# GR_Propu.net
KiCad netlist of a schematic drawn in Altium Designer
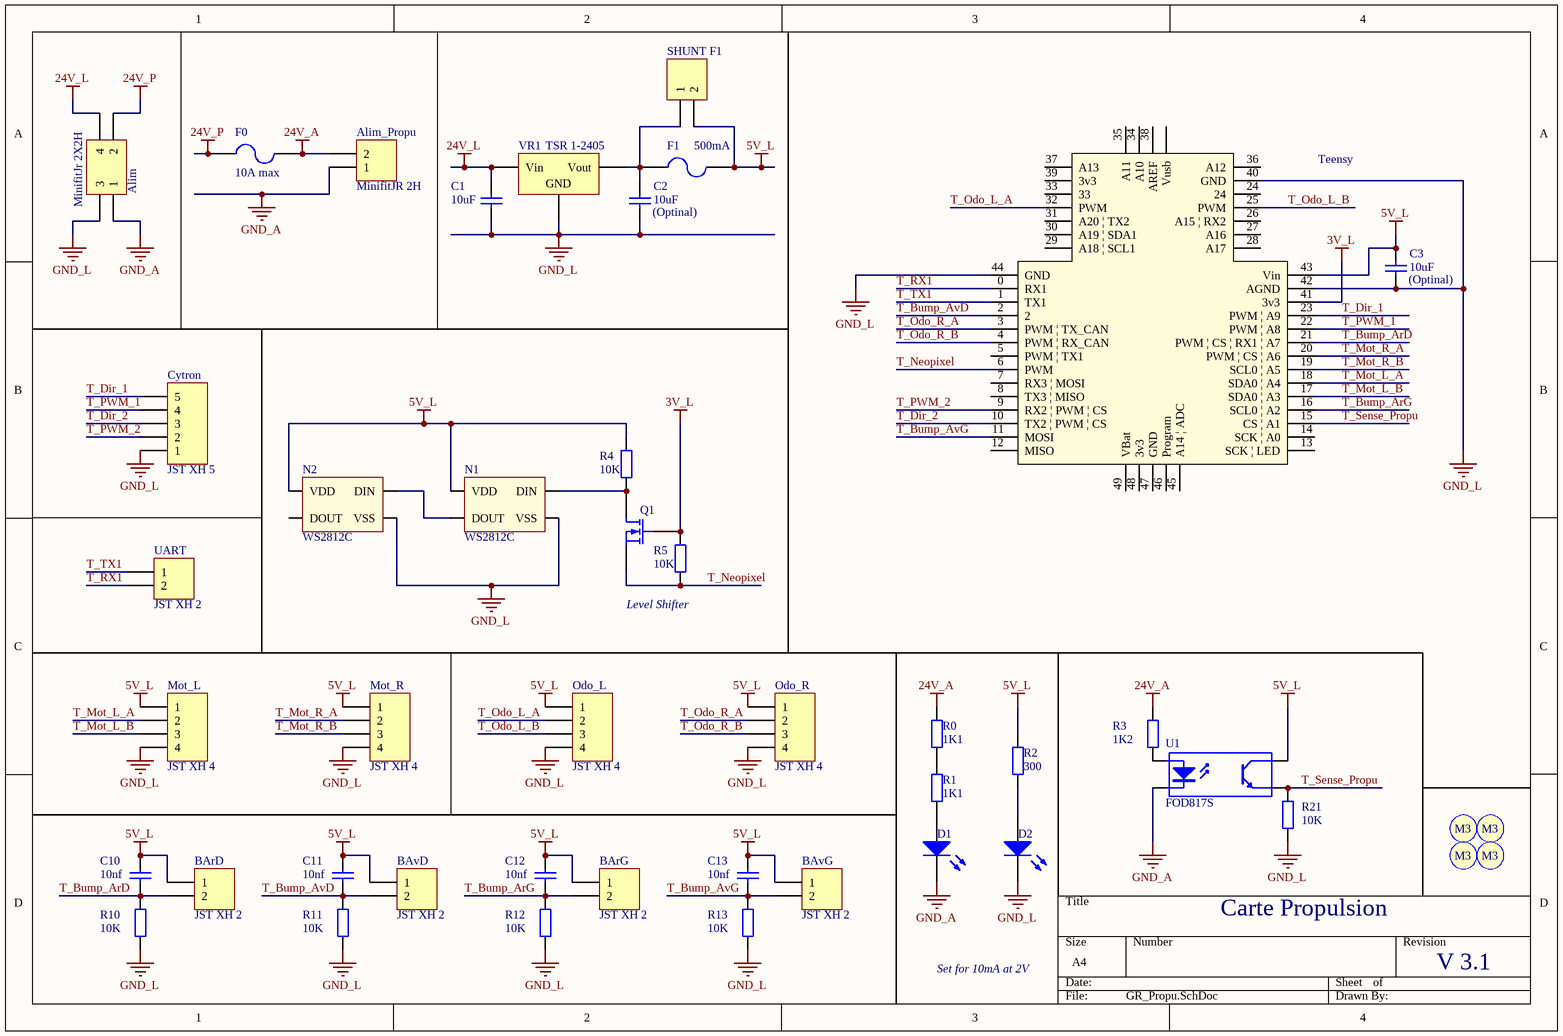
[diagram p0: GR_Propu.SchDoc]

(export (version "E")
  (design (tool "Eeschema 10.0.6"))
  (components
    (comp (ref "Alim")
      (value "MinifitJr 2X2H")
      (footprint "MOLEX_MINIFITJR_2X2H")
      (description "Header, 2-Pin, Dual row, Right Angle")
      (fields (field (name "PUBLISHER") "Altium Limited"))
      (libsource (lib "Miscellaneous Connectors") (part "Header 2X2H"))
    )
    (comp (ref "Alim_Propu")
      (value "MinifitJR 2H")
      (footprint "Molex_MiniFitJr_2x1H")
      (description "Header, 2-Pin")
      (fields (field (name "PUBLISHER") "Altium Limited"))
      (libsource (lib "") (part "Header 2_1"))
    )
    (comp (ref "BArD")
      (value "JST XH 2")
      (footprint "S2B-XH-A")
      (description "Header, 2-Pin")
      (fields (field (name "PUBLISHER") "Altium Limited"))
      (libsource (lib "Miscellaneous Connectors") (part "Header 2"))
    )
    (comp (ref "BArG")
      (value "JST XH 2")
      (footprint "S2B-XH-A")
      (description "Header, 2-Pin")
      (fields (field (name "PUBLISHER") "Altium Limited"))
      (libsource (lib "Miscellaneous Connectors") (part "Header 2"))
    )
    (comp (ref "BAvD")
      (value "JST XH 2")
      (footprint "S2B-XH-A")
      (description "Header, 2-Pin")
      (fields (field (name "PUBLISHER") "Altium Limited"))
      (libsource (lib "Miscellaneous Connectors") (part "Header 2"))
    )
    (comp (ref "BAvG")
      (value "JST XH 2")
      (footprint "S2B-XH-A")
      (description "Header, 2-Pin")
      (fields (field (name "PUBLISHER") "Altium Limited"))
      (libsource (lib "Miscellaneous Connectors") (part "Header 2"))
    )
    (comp (ref "C1")
      (value "10uF")
      (footprint "Capacitor 1206")
      (description "Capacitor")
      (fields (field (name "PUBLISHER") "Altium Limited"))
      (libsource (lib "Miscellaneous Devices") (part "Cap"))
    )
    (comp (ref "C2")
      (value "(Optinal)")
      (footprint "Capacitor 1206")
      (description "Capacitor")
      (fields (field (name "ALTIUM_VALUE") "10uF") (field (name "PUBLISHER") "Altium Limited"))
      (libsource (lib "Miscellaneous Devices") (part "Cap"))
    )
    (comp (ref "C3")
      (value "(Optinal)")
      (footprint "Capacitor 1206")
      (description "Capacitor")
      (fields (field (name "ALTIUM_VALUE") "10uF") (field (name "PUBLISHER") "Altium Limited"))
      (libsource (lib "Miscellaneous Devices") (part "Cap"))
    )
    (comp (ref "C10")
      (value "10nf")
      (footprint "Capacitor 1206")
      (description "Capacitor")
      (fields (field (name "Comment") "Cap") (field (name "PUBLISHER") "Altium Limited"))
      (libsource (lib "Miscellaneous Devices") (part "Cap"))
    )
    (comp (ref "C11")
      (value "10nf")
      (footprint "Capacitor 1206")
      (description "Capacitor")
      (fields (field (name "Comment") "Cap") (field (name "PUBLISHER") "Altium Limited"))
      (libsource (lib "Miscellaneous Devices") (part "Cap"))
    )
    (comp (ref "C12")
      (value "10nf")
      (footprint "Capacitor 1206")
      (description "Capacitor")
      (fields (field (name "Comment") "Cap") (field (name "PUBLISHER") "Altium Limited"))
      (libsource (lib "Miscellaneous Devices") (part "Cap"))
    )
    (comp (ref "C13")
      (value "10nf")
      (footprint "Capacitor 1206")
      (description "Capacitor")
      (fields (field (name "Comment") "Cap") (field (name "PUBLISHER") "Altium Limited"))
      (libsource (lib "Miscellaneous Devices") (part "Cap"))
    )
    (comp (ref "Cytron")
      (value "JST XH 5")
      (footprint "S5B-XH-A")
      (description "Header, 5-Pin")
      (fields (field (name "PUBLISHER") "Altium Limited"))
      (libsource (lib "Miscellaneous Connectors") (part "Header 5"))
    )
    (comp (ref "D1")
      (value "A")
      (footprint "KP-3216SEC")
      (description "Typical RED, GREEN, YELLOW, AMBER GaAs LED")
      (fields (field (name "PUBLISHER") "Altium Limited"))
      (libsource (lib "Miscellaneous Devices") (part "LED2"))
    )
    (comp (ref "D2")
      (value "L")
      (footprint "KP-3216SEC")
      (description "Typical RED, GREEN, YELLOW, AMBER GaAs LED")
      (fields (field (name "PUBLISHER") "Altium Limited"))
      (libsource (lib "Miscellaneous Devices") (part "LED2"))
    )
    (comp (ref "F0")
      (value "10A max")
      (footprint "Fuse")
      (description "Main Fuse")
      (fields (field (name "PUBLISHER") "Altium Limited"))
      (libsource (lib "Miscellaneous Devices") (part "Fuse 2"))
    )
    (comp (ref "F1")
      (value "500mA")
      (footprint "3.5X2.8X1.9")
      (description "Fuse")
      (fields (field (name "PUBLISHER") "Altium Limited"))
      (libsource (lib "Miscellaneous Devices") (part "Fuse 2"))
    )
    (comp (ref "Mot_L")
      (value "JST XH 4")
      (footprint "S4B-XH-A")
      (description "Molex SPOX 4x1H")
      (fields (field (name "PUBLISHER") "Altium Limited"))
      (libsource (lib "Miscellaneous Connectors") (part "Header 4H"))
    )
    (comp (ref "Mot_R")
      (value "JST XH 4")
      (footprint "S4B-XH-A")
      (description "Molex SPOX 4x1H")
      (fields (field (name "PUBLISHER") "Altium Limited"))
      (libsource (lib "Miscellaneous Connectors") (part "Header 4H"))
    )
    (comp (ref "N1")
      (value "WS2812C")
      (footprint "Robot_2020:WS2812C")
      (description "Intelligent control LED")
      (libsource (lib "Robot_2020") (part "WS2812C"))
    )
    (comp (ref "N2")
      (value "WS2812C")
      (footprint "Robot_2020:WS2812C")
      (description "Intelligent control LED")
      (libsource (lib "Robot_2020") (part "WS2812C"))
    )
    (comp (ref "Odo_L")
      (value "JST XH 4")
      (footprint "S4B-XH-A")
      (description "Molex SPOX 4x1H")
      (fields (field (name "PUBLISHER") "Altium Limited"))
      (libsource (lib "Miscellaneous Connectors") (part "Header 4H"))
    )
    (comp (ref "Odo_R")
      (value "JST XH 4")
      (footprint "S4B-XH-A")
      (description "Molex SPOX 4x1H")
      (fields (field (name "PUBLISHER") "Altium Limited"))
      (libsource (lib "Miscellaneous Connectors") (part "Header 4H"))
    )
    (comp (ref "Q1")
      (value "MOSFET-N")
      (footprint "SOT23_M")
      (description "N-Channel MOSFET")
      (fields (field (name "PUBLISHER") "Altium Limited"))
      (libsource (lib "Miscellaneous Devices") (part "MOSFET-N"))
    )
    (comp (ref "R0")
      (value "1K1")
      (footprint "Resistor 1206")
      (description "Resistor")
      (fields (field (name "Comment") "Res2") (field (name "PUBLISHER") "Altium Limited"))
      (libsource (lib "Miscellaneous Devices") (part "Res2"))
    )
    (comp (ref "R1")
      (value "1K1")
      (footprint "Resistor 1206")
      (description "Resistor")
      (fields (field (name "Comment") "Res2") (field (name "PUBLISHER") "Altium Limited"))
      (libsource (lib "Miscellaneous Devices") (part "Res2"))
    )
    (comp (ref "R2")
      (value "300")
      (footprint "Resistor 1206")
      (description "Resistor")
      (fields (field (name "Comment") "Res2") (field (name "PUBLISHER") "Altium Limited"))
      (libsource (lib "Miscellaneous Devices") (part "Res2"))
    )
    (comp (ref "R3")
      (value "1K2")
      (footprint "Resistor 1206")
      (description "Resistor")
      (fields (field (name "Comment") "Res2") (field (name "PUBLISHER") "Altium Limited"))
      (libsource (lib "") (part "Res2_1"))
    )
    (comp (ref "R4")
      (value "10K")
      (footprint "Resistor 1206")
      (description "Resistor")
      (fields (field (name "Comment") "Res2") (field (name "PUBLISHER") "Altium Limited"))
      (libsource (lib "") (part "Res2_1"))
    )
    (comp (ref "R5")
      (value "10K")
      (footprint "Resistor 1206")
      (description "Resistor")
      (fields (field (name "Comment") "Res2") (field (name "PUBLISHER") "Altium Limited"))
      (libsource (lib "") (part "Res2_1"))
    )
    (comp (ref "R10")
      (value "10K")
      (footprint "Resistor 1206")
      (description "Resistor")
      (fields (field (name "Comment") "Res2") (field (name "PUBLISHER") "Altium Limited"))
      (libsource (lib "Miscellaneous Devices") (part "Res2"))
    )
    (comp (ref "R11")
      (value "10K")
      (footprint "Resistor 1206")
      (description "Resistor")
      (fields (field (name "Comment") "Res2") (field (name "PUBLISHER") "Altium Limited"))
      (libsource (lib "Miscellaneous Devices") (part "Res2"))
    )
    (comp (ref "R12")
      (value "10K")
      (footprint "Resistor 1206")
      (description "Resistor")
      (fields (field (name "Comment") "Res2") (field (name "PUBLISHER") "Altium Limited"))
      (libsource (lib "Miscellaneous Devices") (part "Res2"))
    )
    (comp (ref "R13")
      (value "10K")
      (footprint "Resistor 1206")
      (description "Resistor")
      (fields (field (name "Comment") "Res2") (field (name "PUBLISHER") "Altium Limited"))
      (libsource (lib "Miscellaneous Devices") (part "Res2"))
    )
    (comp (ref "R21")
      (value "10K")
      (footprint "Resistor 1206")
      (description "Resistor")
      (fields (field (name "Comment") "Res2") (field (name "PUBLISHER") "Altium Limited"))
      (libsource (lib "") (part "Res2_1"))
    )
    (comp (ref "S1")
      (value "Screw M3")
      (footprint "Screw M3")
      (libsource (lib "Robot_2019") (part "Screw M3"))
    )
    (comp (ref "S2")
      (value "Screw M3")
      (footprint "Screw M3")
      (libsource (lib "Robot_2019") (part "Screw M3"))
    )
    (comp (ref "S3")
      (value "Screw M3")
      (footprint "Screw M3")
      (libsource (lib "Robot_2019") (part "Screw M3"))
    )
    (comp (ref "S4")
      (value "Screw M3")
      (footprint "Screw M3")
      (libsource (lib "Robot_2019") (part "Screw M3"))
    )
    (comp (ref "SHUNT F1")
      (value "Header 2")
      (footprint "HDR1X2")
      (description "Header, 2-Pin")
      (fields (field (name "PUBLISHER") "Altium Limited"))
      (libsource (lib "") (part "Header 2_1"))
    )
    (comp (ref "Teensy")
      (value "Teensy 3.2")
      (footprint "teensy")
      (libsource (lib "Robot_2020") (part "teensy3.2"))
    )
    (comp (ref "U1")
      (value "FOD817S")
      (footprint "SOP254P1016X385-4N")
      (description "4-Pin Phototransistor Optocoupler")
      (fields (field (name "PUBLISHER") "Altium Limited"))
      (libsource (lib "Miscellaneous Devices") (part "Optoisolator1"))
    )
    (comp (ref "UART")
      (value "JST XH 2")
      (footprint "S2B-XH-A")
      (description "Header, 2-Pin")
      (fields (field (name "PUBLISHER") "Altium Limited"))
      (libsource (lib "Miscellaneous Connectors") (part "Header 2"))
    )
    (comp (ref "VR1")
      (value "TSR 1-2405")
      (footprint "TRS")
      (description "Voltage Regulator")
      (fields (field (name "PUBLISHER") "Altium Limited"))
      (libsource (lib "Miscellaneous Devices") (part "Volt Reg"))
    )
  )
  (nets
    (net (code "1") (name "/T_Bump_ArD") (class "Default")
      (node (ref "BArD") (pin "2") (pinfunction "2_2") (pintype "passive"))
      (node (ref "C10") (pin "1") (pinfunction "1_1") (pintype "passive"))
      (node (ref "R10") (pin "1") (pinfunction "1_1") (pintype "passive"))
      (node (ref "Teensy") (pin "21") (pinfunction "PWM_¦_CS_¦_RX1_¦_A7_21") (pintype "passive"))
    )
    (net (code "2") (name "/T_Bump_ArG") (class "Default")
      (node (ref "BArG") (pin "2") (pinfunction "2_2") (pintype "passive"))
      (node (ref "C12") (pin "1") (pinfunction "1_1") (pintype "passive"))
      (node (ref "R12") (pin "1") (pinfunction "1_1") (pintype "passive"))
      (node (ref "Teensy") (pin "16") (pinfunction "SCL0_¦_A2_16") (pintype "passive"))
    )
    (net (code "3") (name "/T_Bump_AvD") (class "Default")
      (node (ref "BAvD") (pin "2") (pinfunction "2_2") (pintype "passive"))
      (node (ref "C11") (pin "1") (pinfunction "1_1") (pintype "passive"))
      (node (ref "R11") (pin "1") (pinfunction "1_1") (pintype "passive"))
      (node (ref "Teensy") (pin "2") (pinfunction "2_2") (pintype "passive"))
    )
    (net (code "4") (name "/T_Bump_AvG") (class "Default")
      (node (ref "BAvG") (pin "2") (pinfunction "2_2") (pintype "passive"))
      (node (ref "C13") (pin "1") (pinfunction "1_1") (pintype "passive"))
      (node (ref "R13") (pin "1") (pinfunction "1_1") (pintype "passive"))
      (node (ref "Teensy") (pin "11") (pinfunction "MOSI_11") (pintype "passive"))
    )
    (net (code "5") (name "/T_Dir_1") (class "Default")
      (node (ref "Cytron") (pin "5") (pinfunction "5_5") (pintype "passive"))
      (node (ref "Teensy") (pin "23") (pinfunction "PWM_¦_A9_23") (pintype "passive"))
    )
    (net (code "6") (name "/T_Dir_2") (class "Default")
      (node (ref "Cytron") (pin "3") (pinfunction "3_3") (pintype "passive"))
      (node (ref "Teensy") (pin "10") (pinfunction "TX2_¦_PWM_¦_CS_10") (pintype "passive"))
    )
    (net (code "7") (name "/T_Mot_L_A") (class "Default")
      (node (ref "Mot_L") (pin "2") (pinfunction "2_2") (pintype "passive"))
      (node (ref "Teensy") (pin "18") (pinfunction "SDA0_¦_A4_18") (pintype "passive"))
    )
    (net (code "8") (name "/T_Mot_L_B") (class "Default")
      (node (ref "Mot_L") (pin "3") (pinfunction "3_3") (pintype "passive"))
      (node (ref "Teensy") (pin "17") (pinfunction "SDA0_¦_A3_17") (pintype "passive"))
    )
    (net (code "9") (name "/T_Mot_R_A") (class "Default")
      (node (ref "Mot_R") (pin "2") (pinfunction "2_2") (pintype "passive"))
      (node (ref "Teensy") (pin "20") (pinfunction "PWM_¦_CS_¦_A6_20") (pintype "passive"))
    )
    (net (code "10") (name "/T_Mot_R_B") (class "Default")
      (node (ref "Mot_R") (pin "3") (pinfunction "3_3") (pintype "passive"))
      (node (ref "Teensy") (pin "19") (pinfunction "SCL0_¦_A5_19") (pintype "passive"))
    )
    (net (code "11") (name "/T_Neopixel") (class "Default")
      (node (ref "Q1") (pin "3") (pinfunction "S_3") (pintype "passive"))
      (node (ref "R5") (pin "1") (pinfunction "1_1") (pintype "passive"))
      (node (ref "Teensy") (pin "6") (pinfunction "PWM_6") (pintype "passive"))
    )
    (net (code "12") (name "/T_Odo_L_A") (class "Default")
      (node (ref "Odo_L") (pin "2") (pinfunction "2_2") (pintype "passive"))
      (node (ref "Teensy") (pin "32") (pinfunction "PWM_32") (pintype "passive"))
    )
    (net (code "13") (name "/T_Odo_L_B") (class "Default")
      (node (ref "Odo_L") (pin "3") (pinfunction "3_3") (pintype "passive"))
      (node (ref "Teensy") (pin "25") (pinfunction "PWM_25") (pintype "passive"))
    )
    (net (code "14") (name "/T_Odo_R_A") (class "Default")
      (node (ref "Odo_R") (pin "2") (pinfunction "2_2") (pintype "passive"))
      (node (ref "Teensy") (pin "3") (pinfunction "PWM_¦_TX_CAN_3") (pintype "passive"))
    )
    (net (code "15") (name "/T_Odo_R_B") (class "Default")
      (node (ref "Odo_R") (pin "3") (pinfunction "3_3") (pintype "passive"))
      (node (ref "Teensy") (pin "4") (pinfunction "PWM_¦_RX_CAN_4") (pintype "passive"))
    )
    (net (code "16") (name "/T_PWM_1") (class "Default")
      (node (ref "Cytron") (pin "4") (pinfunction "4_4") (pintype "passive"))
      (node (ref "Teensy") (pin "22") (pinfunction "PWM_¦_A8_22") (pintype "passive"))
    )
    (net (code "17") (name "/T_PWM_2") (class "Default")
      (node (ref "Cytron") (pin "2") (pinfunction "2_2") (pintype "passive"))
      (node (ref "Teensy") (pin "9") (pinfunction "RX2_¦_PWM_¦_CS_9") (pintype "passive"))
    )
    (net (code "18") (name "/T_RX1") (class "Default")
      (node (ref "Teensy") (pin "0") (pinfunction "RX1_0") (pintype "passive"))
      (node (ref "UART") (pin "2") (pinfunction "2_2") (pintype "passive"))
    )
    (net (code "19") (name "/T_Sense_Propu") (class "Default")
      (node (ref "R21") (pin "2") (pinfunction "2_2") (pintype "passive"))
      (node (ref "Teensy") (pin "15") (pinfunction "CS_¦_A1_15") (pintype "passive"))
      (node (ref "U1") (pin "3") (pinfunction "E_3") (pintype "passive"))
    )
    (net (code "20") (name "/T_TX1") (class "Default")
      (node (ref "Teensy") (pin "1") (pinfunction "TX1_1") (pintype "passive"))
      (node (ref "UART") (pin "1") (pinfunction "1_1") (pintype "passive"))
    )
    (net (code "21") (name "3V_L") (class "Default")
      (node (ref "Q1") (pin "2") (pinfunction "G_2") (pintype "passive"))
      (node (ref "R5") (pin "2") (pinfunction "2_2") (pintype "passive"))
      (node (ref "Teensy") (pin "41") (pinfunction "3v3_41") (pintype "passive"))
    )
    (net (code "22") (name "5V_L") (class "Default")
      (node (ref "BArD") (pin "1") (pinfunction "1_1") (pintype "passive"))
      (node (ref "BArG") (pin "1") (pinfunction "1_1") (pintype "passive"))
      (node (ref "BAvD") (pin "1") (pinfunction "1_1") (pintype "passive"))
      (node (ref "BAvG") (pin "1") (pinfunction "1_1") (pintype "passive"))
      (node (ref "C10") (pin "2") (pinfunction "2_2") (pintype "passive"))
      (node (ref "C11") (pin "2") (pinfunction "2_2") (pintype "passive"))
      (node (ref "C12") (pin "2") (pinfunction "2_2") (pintype "passive"))
      (node (ref "C13") (pin "2") (pinfunction "2_2") (pintype "passive"))
      (node (ref "C3") (pin "2") (pinfunction "2_2") (pintype "passive"))
      (node (ref "F1") (pin "2") (pinfunction "2_2") (pintype "passive"))
      (node (ref "Mot_L") (pin "1") (pinfunction "1_1") (pintype "passive"))
      (node (ref "Mot_R") (pin "1") (pinfunction "1_1") (pintype "passive"))
      (node (ref "N1") (pin "1") (pinfunction "VDD_1") (pintype "passive"))
      (node (ref "N2") (pin "1") (pinfunction "VDD_1") (pintype "passive"))
      (node (ref "Odo_L") (pin "1") (pinfunction "1_1") (pintype "passive"))
      (node (ref "Odo_R") (pin "1") (pinfunction "1_1") (pintype "passive"))
      (node (ref "R2") (pin "1") (pinfunction "1_1") (pintype "passive"))
      (node (ref "R4") (pin "2") (pinfunction "2_2") (pintype "passive"))
      (node (ref "SHUNT F1") (pin "2") (pinfunction "2_2") (pintype "passive"))
      (node (ref "Teensy") (pin "43") (pinfunction "Vin_43") (pintype "passive"))
      (node (ref "U1") (pin "4") (pinfunction "C_4") (pintype "passive"))
    )
    (net (code "23") (name "24V_A") (class "Default")
      (node (ref "Alim_Propu") (pin "2") (pinfunction "2_2") (pintype "passive"))
      (node (ref "F0") (pin "2") (pinfunction "2_2") (pintype "passive"))
      (node (ref "R0") (pin "1") (pinfunction "1_1") (pintype "passive"))
      (node (ref "R3") (pin "2") (pinfunction "2_2") (pintype "passive"))
    )
    (net (code "24") (name "24V_L") (class "Default")
      (node (ref "Alim") (pin "4") (pinfunction "4_4") (pintype "passive"))
      (node (ref "C1") (pin "2") (pinfunction "2_2") (pintype "passive"))
      (node (ref "VR1") (pin "1") (pinfunction "Vin_1") (pintype "passive"))
    )
    (net (code "25") (name "24V_P") (class "Default")
      (node (ref "Alim") (pin "2") (pinfunction "2_2") (pintype "passive"))
      (node (ref "F0") (pin "1") (pinfunction "1_1") (pintype "passive"))
    )
    (net (code "26") (name "GND_A") (class "Default")
      (node (ref "Alim") (pin "1") (pinfunction "1_1") (pintype "passive"))
      (node (ref "Alim_Propu") (pin "1") (pinfunction "1_1") (pintype "passive"))
      (node (ref "D1") (pin "2") (pinfunction "K_2") (pintype "passive"))
      (node (ref "U1") (pin "2") (pinfunction "K_2") (pintype "passive"))
    )
    (net (code "27") (name "GND_L") (class "Default")
      (node (ref "Alim") (pin "3") (pinfunction "3_3") (pintype "passive"))
      (node (ref "C1") (pin "1") (pinfunction "1_1") (pintype "passive"))
      (node (ref "C2") (pin "1") (pinfunction "1_1") (pintype "passive"))
      (node (ref "C3") (pin "1") (pinfunction "1_1") (pintype "passive"))
      (node (ref "Cytron") (pin "1") (pinfunction "1_1") (pintype "passive"))
      (node (ref "D2") (pin "2") (pinfunction "K_2") (pintype "passive"))
      (node (ref "Mot_L") (pin "4") (pinfunction "4_4") (pintype "passive"))
      (node (ref "Mot_R") (pin "4") (pinfunction "4_4") (pintype "passive"))
      (node (ref "N1") (pin "3") (pinfunction "VSS_3") (pintype "passive"))
      (node (ref "N2") (pin "3") (pinfunction "VSS_3") (pintype "passive"))
      (node (ref "Odo_L") (pin "4") (pinfunction "4_4") (pintype "passive"))
      (node (ref "Odo_R") (pin "4") (pinfunction "4_4") (pintype "passive"))
      (node (ref "R10") (pin "2") (pinfunction "2_2") (pintype "passive"))
      (node (ref "R11") (pin "2") (pinfunction "2_2") (pintype "passive"))
      (node (ref "R12") (pin "2") (pinfunction "2_2") (pintype "passive"))
      (node (ref "R13") (pin "2") (pinfunction "2_2") (pintype "passive"))
      (node (ref "R21") (pin "1") (pinfunction "1_1") (pintype "passive"))
      (node (ref "Teensy") (pin "40") (pinfunction "GND_40") (pintype "passive"))
      (node (ref "Teensy") (pin "42") (pinfunction "AGND_42") (pintype "passive"))
      (node (ref "Teensy") (pin "44") (pinfunction "GND_44") (pintype "passive"))
      (node (ref "VR1") (pin "2") (pinfunction "GND_2") (pintype "passive"))
    )
    (net (code "28") (name "Net-(D1-A)") (class "Default")
      (node (ref "D1") (pin "1") (pinfunction "A_1") (pintype "passive"))
      (node (ref "R1") (pin "2") (pinfunction "2_2") (pintype "passive"))
    )
    (net (code "29") (name "Net-(D2-A)") (class "Default")
      (node (ref "D2") (pin "1") (pinfunction "A_1") (pintype "passive"))
      (node (ref "R2") (pin "2") (pinfunction "2_2") (pintype "passive"))
    )
    (net (code "30") (name "Net-(N1-DIN)") (class "Default")
      (node (ref "N1") (pin "4") (pinfunction "DIN_4") (pintype "passive"))
      (node (ref "Q1") (pin "1") (pinfunction "D_1") (pintype "passive"))
      (node (ref "R4") (pin "1") (pinfunction "1_1") (pintype "passive"))
    )
    (net (code "31") (name "Net-(N1-DOUT)") (class "Default")
      (node (ref "N1") (pin "2") (pinfunction "DOUT_2") (pintype "passive"))
      (node (ref "N2") (pin "4") (pinfunction "DIN_4") (pintype "passive"))
    )
    (net (code "32") (name "Net-(R0-Pad2)") (class "Default")
      (node (ref "R0") (pin "2") (pinfunction "2_2") (pintype "passive"))
      (node (ref "R1") (pin "1") (pinfunction "1_1") (pintype "passive"))
    )
    (net (code "33") (name "Net-(U1-A)") (class "Default")
      (node (ref "R3") (pin "1") (pinfunction "1_1") (pintype "passive"))
      (node (ref "U1") (pin "1") (pinfunction "A_1") (pintype "passive"))
    )
    (net (code "34") (name "Net-(VR1-Vout)") (class "Default")
      (node (ref "C2") (pin "2") (pinfunction "2_2") (pintype "passive"))
      (node (ref "F1") (pin "1") (pinfunction "1_1") (pintype "passive"))
      (node (ref "SHUNT F1") (pin "1") (pinfunction "1_1") (pintype "passive"))
      (node (ref "VR1") (pin "3") (pinfunction "Vout_3") (pintype "passive"))
    )
    (net (code "35") (name "unconnected-(N2-DOUT-Pad2)") (class "Default")
      (node (ref "N2") (pin "2") (pinfunction "DOUT_2") (pintype "passive"))
    )
    (net (code "36") (name "unconnected-(Teensy-3v3-Pad39)") (class "Default")
      (node (ref "Teensy") (pin "39") (pinfunction "3v3_39") (pintype "passive"))
    )
    (net (code "37") (name "unconnected-(Teensy-3v3-Pad48)") (class "Default")
      (node (ref "Teensy") (pin "48") (pinfunction "3v3_48") (pintype "passive"))
    )
    (net (code "38") (name "unconnected-(Teensy-A10-Pad34)") (class "Default")
      (node (ref "Teensy") (pin "34") (pinfunction "A10_34") (pintype "passive"))
    )
    (net (code "39") (name "unconnected-(Teensy-A11-Pad35)") (class "Default")
      (node (ref "Teensy") (pin "35") (pinfunction "A11_35") (pintype "passive"))
    )
    (net (code "40") (name "unconnected-(Teensy-A12-Pad36)") (class "Default")
      (node (ref "Teensy") (pin "36") (pinfunction "A12_36") (pintype "passive"))
    )
    (net (code "41") (name "unconnected-(Teensy-A13-Pad37)") (class "Default")
      (node (ref "Teensy") (pin "37") (pinfunction "A13_37") (pintype "passive"))
    )
    (net (code "42") (name "unconnected-(Teensy-A14_¦_ADC-Pad45)") (class "Default")
      (node (ref "Teensy") (pin "45") (pinfunction "A14_¦_ADC_45") (pintype "passive"))
    )
    (net (code "43") (name "unconnected-(Teensy-A15_¦_RX2-Pad26)") (class "Default")
      (node (ref "Teensy") (pin "26") (pinfunction "A15_¦_RX2_26") (pintype "passive"))
    )
    (net (code "44") (name "unconnected-(Teensy-A16-Pad27)") (class "Default")
      (node (ref "Teensy") (pin "27") (pinfunction "A16_27") (pintype "passive"))
    )
    (net (code "45") (name "unconnected-(Teensy-A17-Pad28)") (class "Default")
      (node (ref "Teensy") (pin "28") (pinfunction "A17_28") (pintype "passive"))
    )
    (net (code "46") (name "unconnected-(Teensy-A18_¦_SCL1-Pad29)") (class "Default")
      (node (ref "Teensy") (pin "29") (pinfunction "A18_¦_SCL1_29") (pintype "passive"))
    )
    (net (code "47") (name "unconnected-(Teensy-A19_¦_SDA1-Pad30)") (class "Default")
      (node (ref "Teensy") (pin "30") (pinfunction "A19_¦_SDA1_30") (pintype "passive"))
    )
    (net (code "48") (name "unconnected-(Teensy-A20_¦_TX2-Pad31)") (class "Default")
      (node (ref "Teensy") (pin "31") (pinfunction "A20_¦_TX2_31") (pintype "passive"))
    )
    (net (code "49") (name "unconnected-(Teensy-AREF-Pad38)") (class "Default")
      (node (ref "Teensy") (pin "38") (pinfunction "AREF_38") (pintype "passive"))
    )
    (net (code "50") (name "unconnected-(Teensy-GND-Pad47)") (class "Default")
      (node (ref "Teensy") (pin "47") (pinfunction "GND_47") (pintype "passive"))
    )
    (net (code "51") (name "unconnected-(Teensy-MISO-Pad12)") (class "Default")
      (node (ref "Teensy") (pin "12") (pinfunction "MISO_12") (pintype "passive"))
    )
    (net (code "52") (name "unconnected-(Teensy-PWM_¦_TX1-Pad5)") (class "Default")
      (node (ref "Teensy") (pin "5") (pinfunction "PWM_¦_TX1_5") (pintype "passive"))
    )
    (net (code "53") (name "unconnected-(Teensy-Pad24)") (class "Default")
      (node (ref "Teensy") (pin "24") (pinfunction "24_24") (pintype "passive"))
    )
    (net (code "54") (name "unconnected-(Teensy-Pad33)") (class "Default")
      (node (ref "Teensy") (pin "33") (pinfunction "33_33") (pintype "passive"))
    )
    (net (code "55") (name "unconnected-(Teensy-Program-Pad46)") (class "Default")
      (node (ref "Teensy") (pin "46") (pinfunction "Program_46") (pintype "passive"))
    )
    (net (code "56") (name "unconnected-(Teensy-RX3_¦_MOSI-Pad7)") (class "Default")
      (node (ref "Teensy") (pin "7") (pinfunction "RX3_¦_MOSI_7") (pintype "passive"))
    )
    (net (code "57") (name "unconnected-(Teensy-SCK_¦_A0-Pad14)") (class "Default")
      (node (ref "Teensy") (pin "14") (pinfunction "SCK_¦_A0_14") (pintype "passive"))
    )
    (net (code "58") (name "unconnected-(Teensy-SCK_¦_LED-Pad13)") (class "Default")
      (node (ref "Teensy") (pin "13") (pinfunction "SCK_¦_LED_13") (pintype "passive"))
    )
    (net (code "59") (name "unconnected-(Teensy-TX3_¦_MISO-Pad8)") (class "Default")
      (node (ref "Teensy") (pin "8") (pinfunction "TX3_¦_MISO_8") (pintype "passive"))
    )
    (net (code "60") (name "unconnected-(Teensy-VBat-Pad49)") (class "Default")
      (node (ref "Teensy") (pin "49") (pinfunction "VBat_49") (pintype "passive"))
    )
    (net (code "61") (name "unconnected-(Teensy-Vusb-Pad50)") (class "Default")
      (node (ref "Teensy") (pin "50") (pinfunction "Vusb_50") (pintype "passive"))
    )
  )
)
